# Deathsound_preamp.net
KiCad netlist of a schematic drawn in Altium Designer
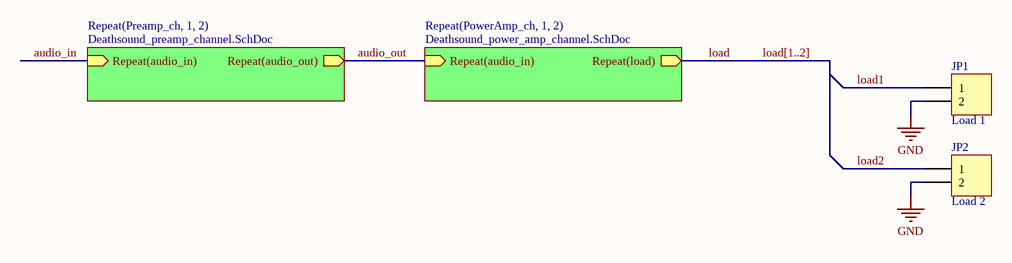
[diagram p0: Deathsound_preamp.SchDoc]

(export (version "E")
  (design (tool "Eeschema 10.0.6"))
  (components
    (comp (ref "JP1")
      (value "Load 1")
      (footprint "HDR1X2")
      (description "Header, 2-Pin")
      (libsource (lib "nucleoduro_lib_audio") (part "Header 2"))
    )
    (comp (ref "JP2")
      (value "Load 2")
      (footprint "HDR1X2")
      (description "Header, 2-Pin")
      (libsource (lib "nucleoduro_lib_audio") (part "Header 2"))
    )
  )
  (nets
    (net (code "4") (name "/load1") (class "Default")
      (node (ref "JP1") (pin "1") (pinfunction "1_1") (pintype "passive"))
    )
    (net (code "5") (name "/load2") (class "Default")
      (node (ref "JP2") (pin "1") (pinfunction "1_1") (pintype "passive"))
    )
    (net (code "7") (name "GND") (class "Default")
      (node (ref "JP1") (pin "2") (pinfunction "2_2") (pintype "passive"))
      (node (ref "JP2") (pin "2") (pinfunction "2_2") (pintype "passive"))
    )
  )
)
